# main.net
KiCad netlist of a schematic drawn in EAGLE
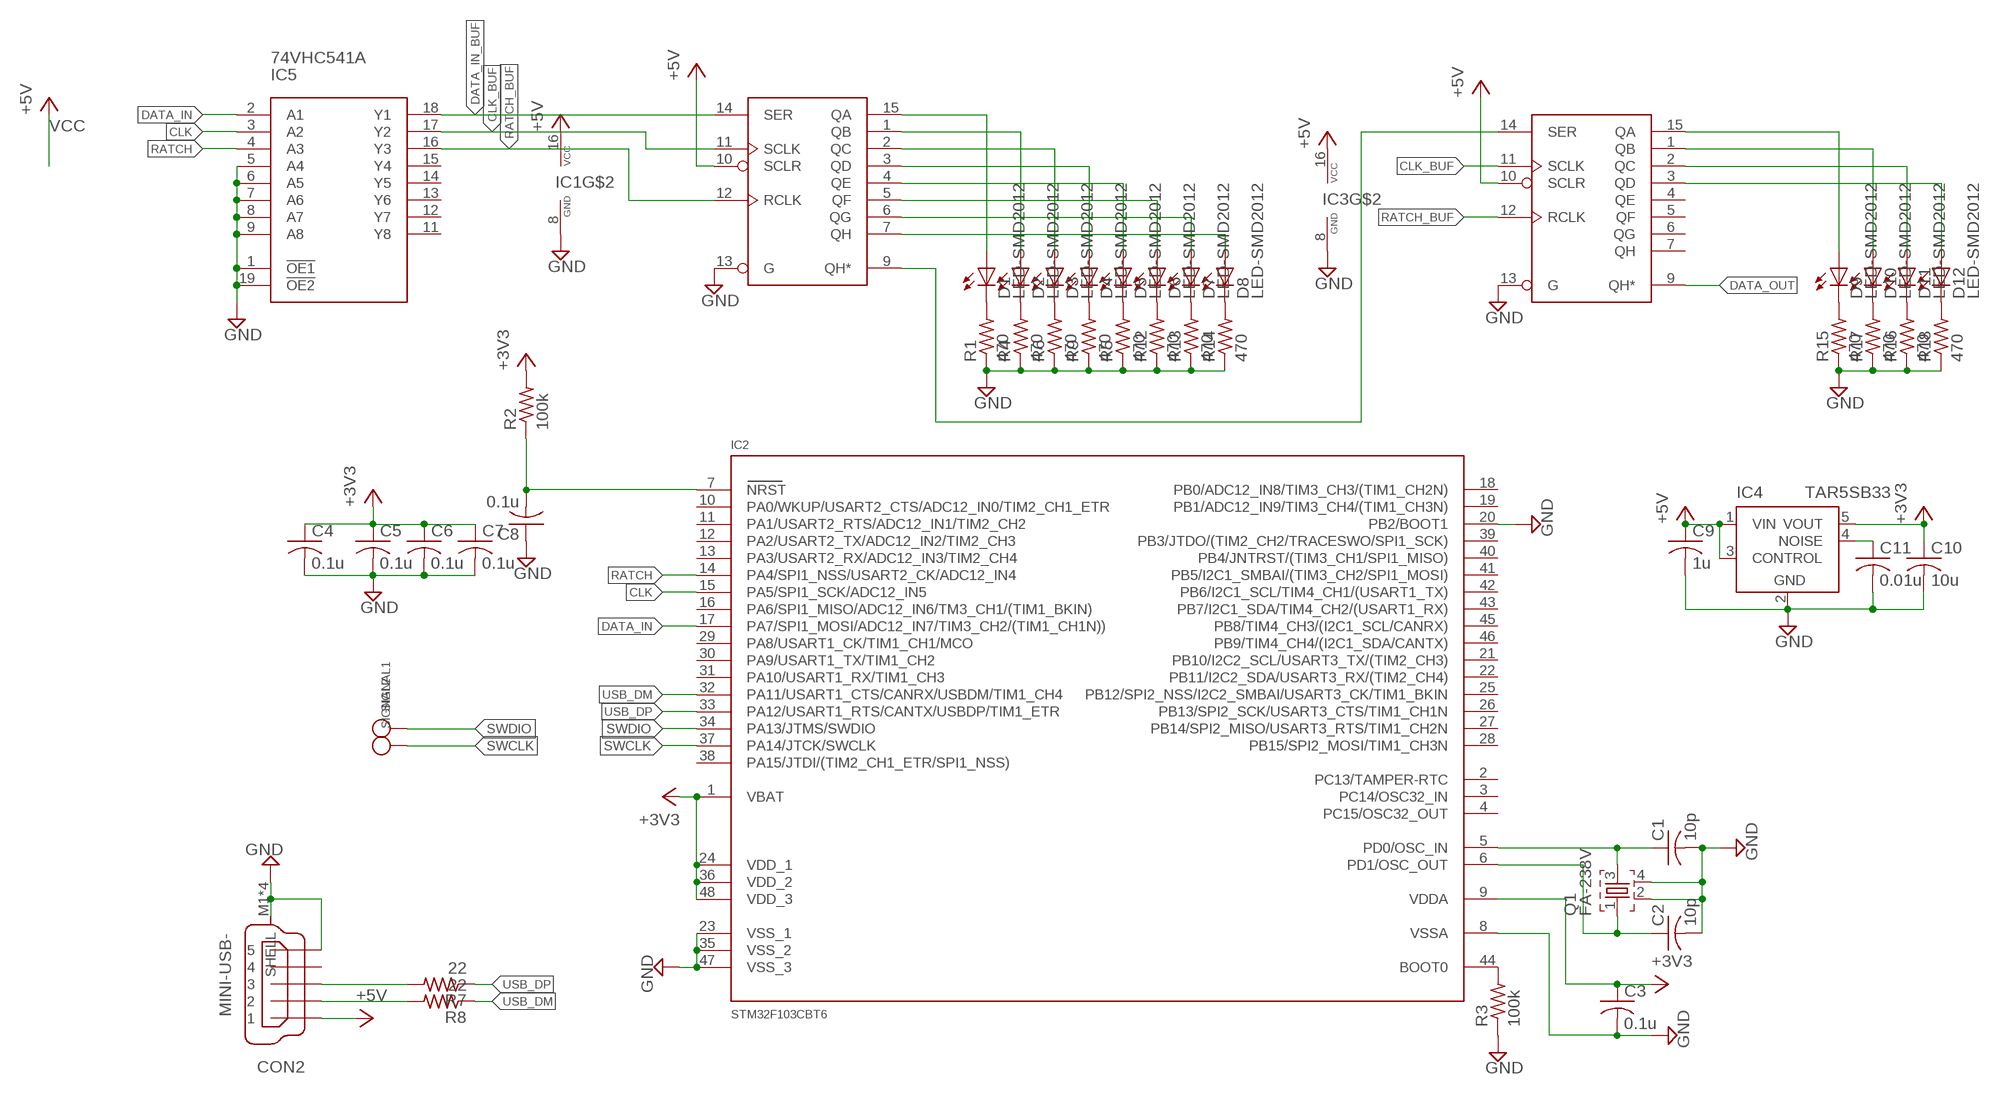
[diagram p0: schematic, sheet 1]

(export (version "E")
  (design (tool "Eeschema 10.0.6"))
  (components
    (comp (ref "C1")
      (value "10p")
      (footprint "eagle-import:1608")
      (libsource (lib "eagle-import") (part "C-1608"))
    )
    (comp (ref "C2")
      (value "10p")
      (footprint "eagle-import:1608")
      (libsource (lib "eagle-import") (part "C-1608"))
    )
    (comp (ref "C3")
      (value "0.1u")
      (footprint "eagle-import:2012-C")
      (libsource (lib "eagle-import") (part "C-2012"))
    )
    (comp (ref "C4")
      (value "0.1u")
      (footprint "eagle-import:2012-C")
      (libsource (lib "eagle-import") (part "C-2012"))
    )
    (comp (ref "C5")
      (value "0.1u")
      (footprint "eagle-import:2012-C")
      (libsource (lib "eagle-import") (part "C-2012"))
    )
    (comp (ref "C6")
      (value "0.1u")
      (footprint "eagle-import:2012-C")
      (libsource (lib "eagle-import") (part "C-2012"))
    )
    (comp (ref "C7")
      (value "0.1u")
      (footprint "eagle-import:2012-C")
      (libsource (lib "eagle-import") (part "C-2012"))
    )
    (comp (ref "C8")
      (value "0.1u")
      (footprint "eagle-import:2012-C")
      (libsource (lib "eagle-import") (part "C-2012"))
    )
    (comp (ref "C9")
      (value "1u")
      (footprint "eagle-import:2012-C")
      (libsource (lib "eagle-import") (part "C-2012"))
    )
    (comp (ref "C10")
      (value "10u")
      (footprint "eagle-import:2012-C")
      (libsource (lib "eagle-import") (part "C-2012"))
    )
    (comp (ref "C11")
      (value "0.01u")
      (footprint "eagle-import:2012-C")
      (libsource (lib "eagle-import") (part "C-2012"))
    )
    (comp (ref "CON2")
      (value "MINI-USB-")
      (footprint "eagle-import:UX60A-MB-5ST")
      (libsource (lib "eagle-import") (part "MINI-USB-"))
    )
    (comp (ref "D1")
      (value "LED-SMD2012")
      (footprint "eagle-import:D2012")
      (libsource (lib "eagle-import") (part "LED-SMD2012"))
    )
    (comp (ref "D2")
      (value "LED-SMD2012")
      (footprint "eagle-import:D2012")
      (libsource (lib "eagle-import") (part "LED-SMD2012"))
    )
    (comp (ref "D3")
      (value "LED-SMD2012")
      (footprint "eagle-import:D2012")
      (libsource (lib "eagle-import") (part "LED-SMD2012"))
    )
    (comp (ref "D4")
      (value "LED-SMD2012")
      (footprint "eagle-import:D2012")
      (libsource (lib "eagle-import") (part "LED-SMD2012"))
    )
    (comp (ref "D5")
      (value "LED-SMD2012")
      (footprint "eagle-import:D2012")
      (libsource (lib "eagle-import") (part "LED-SMD2012"))
    )
    (comp (ref "D6")
      (value "LED-SMD2012")
      (footprint "eagle-import:D2012")
      (libsource (lib "eagle-import") (part "LED-SMD2012"))
    )
    (comp (ref "D7")
      (value "LED-SMD2012")
      (footprint "eagle-import:D2012")
      (libsource (lib "eagle-import") (part "LED-SMD2012"))
    )
    (comp (ref "D8")
      (value "LED-SMD2012")
      (footprint "eagle-import:D2012")
      (libsource (lib "eagle-import") (part "LED-SMD2012"))
    )
    (comp (ref "D9")
      (value "LED-SMD2012")
      (footprint "eagle-import:D2012")
      (libsource (lib "eagle-import") (part "LED-SMD2012"))
    )
    (comp (ref "D10")
      (value "LED-SMD2012")
      (footprint "eagle-import:D2012")
      (libsource (lib "eagle-import") (part "LED-SMD2012"))
    )
    (comp (ref "D11")
      (value "LED-SMD2012")
      (footprint "eagle-import:D2012")
      (libsource (lib "eagle-import") (part "LED-SMD2012"))
    )
    (comp (ref "D12")
      (value "LED-SMD2012")
      (footprint "eagle-import:D2012")
      (libsource (lib "eagle-import") (part "LED-SMD2012"))
    )
    (comp (ref "IC1")
      (value "74595AP")
      (footprint "eagle-import:SOP16")
      (libsource (lib "eagle-import") (part "74595AP"))
    )
    (comp (ref "IC2")
      (value "STM32F103CBT6")
      (footprint "eagle-import:LQFP48")
      (libsource (lib "eagle-import") (part "STM32F103CBT6"))
    )
    (comp (ref "IC3")
      (value "74595AP")
      (footprint "eagle-import:SOP16")
      (libsource (lib "eagle-import") (part "74595AP"))
    )
    (comp (ref "IC4")
      (value "TAR5SB33")
      (footprint "eagle-import:SSOP5-P-0.95")
      (libsource (lib "eagle-import") (part "TAR5SB33"))
    )
    (comp (ref "IC5")
      (value "74VHC541A")
      (footprint "eagle-import:TSSOP20")
      (libsource (lib "eagle-import") (part "74541AVHC"))
    )
    (comp (ref "Q1")
      (value "FA-238V")
      (footprint "eagle-import:FA-238V")
      (libsource (lib "eagle-import") (part "FA-238V"))
    )
    (comp (ref "R1")
      (value "470")
      (footprint "eagle-import:2012-R")
      (libsource (lib "eagle-import") (part "R-2012"))
    )
    (comp (ref "R2")
      (value "100k")
      (footprint "eagle-import:2012-R")
      (libsource (lib "eagle-import") (part "R-2012"))
    )
    (comp (ref "R3")
      (value "100k")
      (footprint "eagle-import:2012-R")
      (libsource (lib "eagle-import") (part "R-2012"))
    )
    (comp (ref "R4")
      (value "470")
      (footprint "eagle-import:2012-R")
      (libsource (lib "eagle-import") (part "R-2012"))
    )
    (comp (ref "R5")
      (value "470")
      (footprint "eagle-import:2012-R")
      (libsource (lib "eagle-import") (part "R-2012"))
    )
    (comp (ref "R6")
      (value "470")
      (footprint "eagle-import:2012-R")
      (libsource (lib "eagle-import") (part "R-2012"))
    )
    (comp (ref "R7")
      (value "22")
      (footprint "eagle-import:2012-R")
      (libsource (lib "eagle-import") (part "R-2012"))
    )
    (comp (ref "R8")
      (value "22")
      (footprint "eagle-import:2012-R")
      (libsource (lib "eagle-import") (part "R-2012"))
    )
    (comp (ref "R9")
      (value "470")
      (footprint "eagle-import:2012-R")
      (libsource (lib "eagle-import") (part "R-2012"))
    )
    (comp (ref "R12")
      (value "470")
      (footprint "eagle-import:2012-R")
      (libsource (lib "eagle-import") (part "R-2012"))
    )
    (comp (ref "R13")
      (value "470")
      (footprint "eagle-import:2012-R")
      (libsource (lib "eagle-import") (part "R-2012"))
    )
    (comp (ref "R14")
      (value "470")
      (footprint "eagle-import:2012-R")
      (libsource (lib "eagle-import") (part "R-2012"))
    )
    (comp (ref "R15")
      (value "470")
      (footprint "eagle-import:2012-R")
      (libsource (lib "eagle-import") (part "R-2012"))
    )
    (comp (ref "R16")
      (value "470")
      (footprint "eagle-import:2012-R")
      (libsource (lib "eagle-import") (part "R-2012"))
    )
    (comp (ref "R17")
      (value "470")
      (footprint "eagle-import:2012-R")
      (libsource (lib "eagle-import") (part "R-2012"))
    )
    (comp (ref "R18")
      (value "470")
      (footprint "eagle-import:2012-R")
      (libsource (lib "eagle-import") (part "R-2012"))
    )
    (comp (ref "SIGNAL1")
      (value "CHECK_PIN-SMD_100*60")
      (footprint "eagle-import:SMD_100_60")
      (libsource (lib "eagle-import") (part "CHECK_PIN-SMD_10060"))
    )
    (comp (ref "SIGNAL2")
      (value "CHECK_PIN-SMD_100*60")
      (footprint "eagle-import:SMD_100_60")
      (libsource (lib "eagle-import") (part "CHECK_PIN-SMD_10060"))
    )
  )
  (nets
    (net (code "1") (name "+3V3") (class "Default")
      (node (ref "C10") (pin "1") (pinfunction "1_1") (pintype "passive"))
      (node (ref "C3") (pin "1") (pinfunction "1_1") (pintype "passive"))
      (node (ref "C4") (pin "1") (pinfunction "1_1") (pintype "passive"))
      (node (ref "C5") (pin "1") (pinfunction "1_1") (pintype "passive"))
      (node (ref "C6") (pin "1") (pinfunction "1_1") (pintype "passive"))
      (node (ref "C7") (pin "1") (pinfunction "1_1") (pintype "passive"))
      (node (ref "IC2") (pin "1") (pinfunction "VBAT_1") (pintype "power_in"))
      (node (ref "IC2") (pin "24") (pinfunction "VDD_1_24") (pintype "power_in"))
      (node (ref "IC2") (pin "36") (pinfunction "VDD_2_36") (pintype "power_in"))
      (node (ref "IC2") (pin "48") (pinfunction "VDD_3_48") (pintype "power_in"))
      (node (ref "IC2") (pin "9") (pinfunction "VDDA_9") (pintype "power_in"))
      (node (ref "IC4") (pin "5") (pinfunction "VOUT_5") (pintype "power_in"))
      (node (ref "R2") (pin "2") (pinfunction "2_2") (pintype "passive"))
    )
    (net (code "2") (name "+5V") (class "Default")
      (node (ref "C9") (pin "1") (pinfunction "1_1") (pintype "passive"))
      (node (ref "CON2") (pin "1") (pinfunction "1_1") (pintype "input"))
      (node (ref "IC1") (pin "10") (pinfunction "SCLR_10") (pintype "input"))
      (node (ref "IC1") (pin "16") (pinfunction "VCC_16") (pintype "power_in"))
      (node (ref "IC3") (pin "10") (pinfunction "SCLR_10") (pintype "input"))
      (node (ref "IC3") (pin "16") (pinfunction "VCC_16") (pintype "power_in"))
      (node (ref "IC4") (pin "1") (pinfunction "VIN_1") (pintype "input"))
      (node (ref "IC4") (pin "3") (pinfunction "CONTROL_3") (pintype "input"))
    )
    (net (code "3") (name "CLK") (class "Default")
      (node (ref "IC2") (pin "15") (pinfunction "PA5/SPI1_SCK/ADC12_IN5_15") (pintype "bidirectional"))
      (node (ref "IC5") (pin "3") (pinfunction "A2_3") (pintype "bidirectional"))
    )
    (net (code "4") (name "CLK_BUF") (class "Default")
      (node (ref "IC1") (pin "11") (pinfunction "SCLK_11") (pintype "input"))
      (node (ref "IC3") (pin "11") (pinfunction "SCLK_11") (pintype "input"))
      (node (ref "IC5") (pin "17") (pinfunction "Y2_17") (pintype "bidirectional"))
    )
    (net (code "5") (name "DATA_IN") (class "Default")
      (node (ref "IC2") (pin "17") (pinfunction "PA7/SPI1_MOSI/ADC12_IN7/TIM3_CH2/(TIM1_CH1N))_17") (pintype "bidirectional"))
      (node (ref "IC5") (pin "2") (pinfunction "A1_2") (pintype "bidirectional"))
    )
    (net (code "6") (name "DATA_IN_BUF") (class "Default")
      (node (ref "IC1") (pin "14") (pinfunction "SER_14") (pintype "input"))
      (node (ref "IC5") (pin "18") (pinfunction "Y1_18") (pintype "bidirectional"))
    )
    (net (code "7") (name "DATA_OUT") (class "Default")
      (node (ref "IC3") (pin "9") (pinfunction "QH*_9") (pintype "output"))
    )
    (net (code "8") (name "GND") (class "Default")
      (node (ref "C1") (pin "2") (pinfunction "2_2") (pintype "passive"))
      (node (ref "C10") (pin "2") (pinfunction "2_2") (pintype "passive"))
      (node (ref "C11") (pin "2") (pinfunction "2_2") (pintype "passive"))
      (node (ref "C2") (pin "2") (pinfunction "2_2") (pintype "passive"))
      (node (ref "C3") (pin "2") (pinfunction "2_2") (pintype "passive"))
      (node (ref "C4") (pin "2") (pinfunction "2_2") (pintype "passive"))
      (node (ref "C5") (pin "2") (pinfunction "2_2") (pintype "passive"))
      (node (ref "C6") (pin "2") (pinfunction "2_2") (pintype "passive"))
      (node (ref "C7") (pin "2") (pinfunction "2_2") (pintype "passive"))
      (node (ref "C8") (pin "1") (pinfunction "1_1") (pintype "passive"))
      (node (ref "C9") (pin "2") (pinfunction "2_2") (pintype "passive"))
      (node (ref "CON2") (pin "5") (pinfunction "5_5") (pintype "input"))
      (node (ref "CON2") (pin "M1") (pinfunction "SHELL_M1") (pintype "bidirectional"))
      (node (ref "CON2") (pin "M2") (pinfunction "SHELL_M2") (pintype "bidirectional"))
      (node (ref "CON2") (pin "M3") (pinfunction "SHELL_M3") (pintype "bidirectional"))
      (node (ref "CON2") (pin "M4") (pinfunction "SHELL_M4") (pintype "bidirectional"))
      (node (ref "IC1") (pin "13") (pinfunction "G_13") (pintype "input"))
      (node (ref "IC1") (pin "8") (pinfunction "GND_8") (pintype "power_in"))
      (node (ref "IC2") (pin "20") (pinfunction "PB2/BOOT1_20") (pintype "bidirectional"))
      (node (ref "IC2") (pin "23") (pinfunction "VSS_1_23") (pintype "power_in"))
      (node (ref "IC2") (pin "35") (pinfunction "VSS_2_35") (pintype "power_in"))
      (node (ref "IC2") (pin "47") (pinfunction "VSS_3_47") (pintype "power_in"))
      (node (ref "IC2") (pin "8") (pinfunction "VSSA_8") (pintype "power_in"))
      (node (ref "IC3") (pin "13") (pinfunction "G_13") (pintype "input"))
      (node (ref "IC3") (pin "8") (pinfunction "GND_8") (pintype "power_in"))
      (node (ref "IC4") (pin "2") (pinfunction "GND_2") (pintype "power_in"))
      (node (ref "IC5") (pin "1") (pinfunction "~{OE1}_1") (pintype "bidirectional"))
      (node (ref "IC5") (pin "19") (pinfunction "~{OE2}_19") (pintype "bidirectional"))
      (node (ref "IC5") (pin "5") (pinfunction "A4_5") (pintype "bidirectional"))
      (node (ref "IC5") (pin "6") (pinfunction "A5_6") (pintype "bidirectional"))
      (node (ref "IC5") (pin "7") (pinfunction "A6_7") (pintype "bidirectional"))
      (node (ref "IC5") (pin "8") (pinfunction "A7_8") (pintype "bidirectional"))
      (node (ref "IC5") (pin "9") (pinfunction "A8_9") (pintype "bidirectional"))
      (node (ref "Q1") (pin "2") (pinfunction "2_2") (pintype "passive"))
      (node (ref "Q1") (pin "4") (pinfunction "4_4") (pintype "passive"))
      (node (ref "R1") (pin "1") (pinfunction "1_1") (pintype "passive"))
      (node (ref "R12") (pin "1") (pinfunction "1_1") (pintype "passive"))
      (node (ref "R13") (pin "1") (pinfunction "1_1") (pintype "passive"))
      (node (ref "R14") (pin "1") (pinfunction "1_1") (pintype "passive"))
      (node (ref "R15") (pin "1") (pinfunction "1_1") (pintype "passive"))
      (node (ref "R16") (pin "1") (pinfunction "1_1") (pintype "passive"))
      (node (ref "R17") (pin "1") (pinfunction "1_1") (pintype "passive"))
      (node (ref "R18") (pin "1") (pinfunction "1_1") (pintype "passive"))
      (node (ref "R3") (pin "1") (pinfunction "1_1") (pintype "passive"))
      (node (ref "R4") (pin "1") (pinfunction "1_1") (pintype "passive"))
      (node (ref "R5") (pin "1") (pinfunction "1_1") (pintype "passive"))
      (node (ref "R6") (pin "1") (pinfunction "1_1") (pintype "passive"))
      (node (ref "R9") (pin "1") (pinfunction "1_1") (pintype "passive"))
    )
    (net (code "9") (name "Net-(CON2-Pad2)") (class "Default")
      (node (ref "CON2") (pin "2") (pinfunction "2_2") (pintype "input"))
      (node (ref "R8") (pin "2") (pinfunction "2_2") (pintype "passive"))
    )
    (net (code "10") (name "Net-(CON2-Pad3)") (class "Default")
      (node (ref "CON2") (pin "3") (pinfunction "3_3") (pintype "input"))
      (node (ref "R7") (pin "2") (pinfunction "2_2") (pintype "passive"))
    )
    (net (code "11") (name "Net-(D1-PadK)") (class "Default")
      (node (ref "D1") (pin "K") (pinfunction "K_K") (pintype "passive"))
      (node (ref "R1") (pin "2") (pinfunction "2_2") (pintype "passive"))
    )
    (net (code "12") (name "Net-(D2-PadK)") (class "Default")
      (node (ref "D2") (pin "K") (pinfunction "K_K") (pintype "passive"))
      (node (ref "R4") (pin "2") (pinfunction "2_2") (pintype "passive"))
    )
    (net (code "13") (name "Net-(D3-PadK)") (class "Default")
      (node (ref "D3") (pin "K") (pinfunction "K_K") (pintype "passive"))
      (node (ref "R6") (pin "2") (pinfunction "2_2") (pintype "passive"))
    )
    (net (code "14") (name "Net-(D4-PadK)") (class "Default")
      (node (ref "D4") (pin "K") (pinfunction "K_K") (pintype "passive"))
      (node (ref "R9") (pin "2") (pinfunction "2_2") (pintype "passive"))
    )
    (net (code "15") (name "Net-(D5-PadK)") (class "Default")
      (node (ref "D5") (pin "K") (pinfunction "K_K") (pintype "passive"))
      (node (ref "R5") (pin "2") (pinfunction "2_2") (pintype "passive"))
    )
    (net (code "16") (name "Net-(D6-PadK)") (class "Default")
      (node (ref "D6") (pin "K") (pinfunction "K_K") (pintype "passive"))
      (node (ref "R12") (pin "2") (pinfunction "2_2") (pintype "passive"))
    )
    (net (code "17") (name "Net-(D7-PadK)") (class "Default")
      (node (ref "D7") (pin "K") (pinfunction "K_K") (pintype "passive"))
      (node (ref "R13") (pin "2") (pinfunction "2_2") (pintype "passive"))
    )
    (net (code "18") (name "Net-(D8-PadK)") (class "Default")
      (node (ref "D8") (pin "K") (pinfunction "K_K") (pintype "passive"))
      (node (ref "R14") (pin "2") (pinfunction "2_2") (pintype "passive"))
    )
    (net (code "19") (name "Net-(D9-PadK)") (class "Default")
      (node (ref "D9") (pin "K") (pinfunction "K_K") (pintype "passive"))
      (node (ref "R15") (pin "2") (pinfunction "2_2") (pintype "passive"))
    )
    (net (code "20") (name "Net-(D10-PadK)") (class "Default")
      (node (ref "D10") (pin "K") (pinfunction "K_K") (pintype "passive"))
      (node (ref "R17") (pin "2") (pinfunction "2_2") (pintype "passive"))
    )
    (net (code "21") (name "Net-(D11-PadK)") (class "Default")
      (node (ref "D11") (pin "K") (pinfunction "K_K") (pintype "passive"))
      (node (ref "R16") (pin "2") (pinfunction "2_2") (pintype "passive"))
    )
    (net (code "22") (name "Net-(D12-PadK)") (class "Default")
      (node (ref "D12") (pin "K") (pinfunction "K_K") (pintype "passive"))
      (node (ref "R18") (pin "2") (pinfunction "2_2") (pintype "passive"))
    )
    (net (code "23") (name "Net-(IC1A-QA)") (class "Default")
      (node (ref "D1") (pin "A") (pinfunction "A_A") (pintype "passive"))
      (node (ref "IC1") (pin "15") (pinfunction "QA_15") (pintype "output"))
    )
    (net (code "24") (name "Net-(IC1A-QB)") (class "Default")
      (node (ref "D2") (pin "A") (pinfunction "A_A") (pintype "passive"))
      (node (ref "IC1") (pin "1") (pinfunction "QB_1") (pintype "output"))
    )
    (net (code "25") (name "Net-(IC1A-QC)") (class "Default")
      (node (ref "D3") (pin "A") (pinfunction "A_A") (pintype "passive"))
      (node (ref "IC1") (pin "2") (pinfunction "QC_2") (pintype "output"))
    )
    (net (code "26") (name "Net-(IC1A-QD)") (class "Default")
      (node (ref "D4") (pin "A") (pinfunction "A_A") (pintype "passive"))
      (node (ref "IC1") (pin "3") (pinfunction "QD_3") (pintype "output"))
    )
    (net (code "27") (name "Net-(IC1A-QE)") (class "Default")
      (node (ref "D5") (pin "A") (pinfunction "A_A") (pintype "passive"))
      (node (ref "IC1") (pin "4") (pinfunction "QE_4") (pintype "output"))
    )
    (net (code "28") (name "Net-(IC1A-QF)") (class "Default")
      (node (ref "D6") (pin "A") (pinfunction "A_A") (pintype "passive"))
      (node (ref "IC1") (pin "5") (pinfunction "QF_5") (pintype "output"))
    )
    (net (code "29") (name "Net-(IC1A-QG)") (class "Default")
      (node (ref "D7") (pin "A") (pinfunction "A_A") (pintype "passive"))
      (node (ref "IC1") (pin "6") (pinfunction "QG_6") (pintype "output"))
    )
    (net (code "30") (name "Net-(IC1A-QH)") (class "Default")
      (node (ref "D8") (pin "A") (pinfunction "A_A") (pintype "passive"))
      (node (ref "IC1") (pin "7") (pinfunction "QH_7") (pintype "output"))
    )
    (net (code "31") (name "Net-(IC1A-QH*)") (class "Default")
      (node (ref "IC1") (pin "9") (pinfunction "QH*_9") (pintype "output"))
      (node (ref "IC3") (pin "14") (pinfunction "SER_14") (pintype "input"))
    )
    (net (code "32") (name "Net-(IC2-BOOT0)") (class "Default")
      (node (ref "IC2") (pin "44") (pinfunction "BOOT0_44") (pintype "input"))
      (node (ref "R3") (pin "2") (pinfunction "2_2") (pintype "passive"))
    )
    (net (code "33") (name "Net-(IC2-NRST)") (class "Default")
      (node (ref "C8") (pin "2") (pinfunction "2_2") (pintype "passive"))
      (node (ref "IC2") (pin "7") (pinfunction "NRST_7") (pintype "bidirectional"))
      (node (ref "R2") (pin "1") (pinfunction "1_1") (pintype "passive"))
    )
    (net (code "34") (name "Net-(IC2-PD0{slash}OSC_IN)") (class "Default")
      (node (ref "C1") (pin "1") (pinfunction "1_1") (pintype "passive"))
      (node (ref "IC2") (pin "5") (pinfunction "PD0/OSC_IN_5") (pintype "bidirectional"))
      (node (ref "Q1") (pin "3") (pinfunction "3_3") (pintype "passive"))
    )
    (net (code "35") (name "Net-(IC2-PD1{slash}OSC_OUT)") (class "Default")
      (node (ref "C2") (pin "1") (pinfunction "1_1") (pintype "passive"))
      (node (ref "IC2") (pin "6") (pinfunction "PD1/OSC_OUT_6") (pintype "bidirectional"))
      (node (ref "Q1") (pin "1") (pinfunction "1_1") (pintype "passive"))
    )
    (net (code "36") (name "Net-(IC3A-QA)") (class "Default")
      (node (ref "D9") (pin "A") (pinfunction "A_A") (pintype "passive"))
      (node (ref "IC3") (pin "15") (pinfunction "QA_15") (pintype "output"))
    )
    (net (code "37") (name "Net-(IC3A-QB)") (class "Default")
      (node (ref "D10") (pin "A") (pinfunction "A_A") (pintype "passive"))
      (node (ref "IC3") (pin "1") (pinfunction "QB_1") (pintype "output"))
    )
    (net (code "38") (name "Net-(IC3A-QC)") (class "Default")
      (node (ref "D11") (pin "A") (pinfunction "A_A") (pintype "passive"))
      (node (ref "IC3") (pin "2") (pinfunction "QC_2") (pintype "output"))
    )
    (net (code "39") (name "Net-(IC3A-QD)") (class "Default")
      (node (ref "D12") (pin "A") (pinfunction "A_A") (pintype "passive"))
      (node (ref "IC3") (pin "3") (pinfunction "QD_3") (pintype "output"))
    )
    (net (code "40") (name "Net-(IC4-NOISE)") (class "Default")
      (node (ref "C11") (pin "1") (pinfunction "1_1") (pintype "passive"))
      (node (ref "IC4") (pin "4") (pinfunction "NOISE_4") (pintype "passive"))
    )
    (net (code "41") (name "RATCH") (class "Default")
      (node (ref "IC2") (pin "14") (pinfunction "PA4/SPI1_NSS/USART2_CK/ADC12_IN4_14") (pintype "bidirectional"))
      (node (ref "IC5") (pin "4") (pinfunction "A3_4") (pintype "bidirectional"))
    )
    (net (code "42") (name "RATCH_BUF") (class "Default")
      (node (ref "IC1") (pin "12") (pinfunction "RCLK_12") (pintype "input"))
      (node (ref "IC3") (pin "12") (pinfunction "RCLK_12") (pintype "input"))
      (node (ref "IC5") (pin "16") (pinfunction "Y3_16") (pintype "bidirectional"))
    )
    (net (code "43") (name "SWCLK") (class "Default")
      (node (ref "IC2") (pin "37") (pinfunction "PA14/JTCK/SWCLK_37") (pintype "bidirectional"))
      (node (ref "SIGNAL2") (pin "SIGNAL") (pinfunction "SIGNAL_SIGNAL") (pintype "bidirectional"))
    )
    (net (code "44") (name "SWDIO") (class "Default")
      (node (ref "IC2") (pin "34") (pinfunction "PA13/JTMS/SWDIO_34") (pintype "bidirectional"))
      (node (ref "SIGNAL1") (pin "SIGNAL") (pinfunction "SIGNAL_SIGNAL") (pintype "bidirectional"))
    )
    (net (code "45") (name "USB_DM") (class "Default")
      (node (ref "IC2") (pin "32") (pinfunction "PA11/USART1_CTS/CANRX/USBDM/TIM1_CH4_32") (pintype "bidirectional"))
      (node (ref "R8") (pin "1") (pinfunction "1_1") (pintype "passive"))
    )
    (net (code "46") (name "USB_DP") (class "Default")
      (node (ref "IC2") (pin "33") (pinfunction "PA12/USART1_RTS/CANTX/USBDP/TIM1_ETR_33") (pintype "bidirectional"))
      (node (ref "R7") (pin "1") (pinfunction "1_1") (pintype "passive"))
    )
    (net (code "47") (name "unconnected-(CON2-Pad4)") (class "Default")
      (node (ref "CON2") (pin "4") (pinfunction "4_4") (pintype "input"))
    )
    (net (code "48") (name "unconnected-(IC2-PA0{slash}WKUP{slash}USART2_CTS{slash}ADC12_IN0{slash}TIM2_CH1_ETR-Pad10)") (class "Default")
      (node (ref "IC2") (pin "10") (pinfunction "PA0/WKUP/USART2_CTS/ADC12_IN0/TIM2_CH1_ETR_10") (pintype "bidirectional"))
    )
    (net (code "49") (name "unconnected-(IC2-PA1{slash}USART2_RTS{slash}ADC12_IN1{slash}TIM2_CH2-Pad11)") (class "Default")
      (node (ref "IC2") (pin "11") (pinfunction "PA1/USART2_RTS/ADC12_IN1/TIM2_CH2_11") (pintype "bidirectional"))
    )
    (net (code "50") (name "unconnected-(IC2-PA2{slash}USART2_TX{slash}ADC12_IN2{slash}TIM2_CH3-Pad12)") (class "Default")
      (node (ref "IC2") (pin "12") (pinfunction "PA2/USART2_TX/ADC12_IN2/TIM2_CH3_12") (pintype "bidirectional"))
    )
    (net (code "51") (name "unconnected-(IC2-PA3{slash}USART2_RX{slash}ADC12_IN3{slash}TIM2_CH4-Pad13)") (class "Default")
      (node (ref "IC2") (pin "13") (pinfunction "PA3/USART2_RX/ADC12_IN3/TIM2_CH4_13") (pintype "bidirectional"))
    )
    (net (code "52") (name "unconnected-(IC2-PA6{slash}SPI1_MISO{slash}ADC12_IN6{slash}TM3_CH1{slash}(TIM1_BKIN)-Pad16)") (class "Default")
      (node (ref "IC2") (pin "16") (pinfunction "PA6/SPI1_MISO/ADC12_IN6/TM3_CH1/(TIM1_BKIN)_16") (pintype "bidirectional"))
    )
    (net (code "53") (name "unconnected-(IC2-PA8{slash}USART1_CK{slash}TIM1_CH1{slash}MCO-Pad29)") (class "Default")
      (node (ref "IC2") (pin "29") (pinfunction "PA8/USART1_CK/TIM1_CH1/MCO_29") (pintype "bidirectional"))
    )
    (net (code "54") (name "unconnected-(IC2-PA9{slash}USART1_TX{slash}TIM1_CH2-Pad30)") (class "Default")
      (node (ref "IC2") (pin "30") (pinfunction "PA9/USART1_TX/TIM1_CH2_30") (pintype "bidirectional"))
    )
    (net (code "55") (name "unconnected-(IC2-PA10{slash}USART1_RX{slash}TIM1_CH3-Pad31)") (class "Default")
      (node (ref "IC2") (pin "31") (pinfunction "PA10/USART1_RX/TIM1_CH3_31") (pintype "bidirectional"))
    )
    (net (code "56") (name "unconnected-(IC2-PA15{slash}JTDI{slash}(TIM2_CH1_ETR{slash}SPI1_NSS)-Pad38)") (class "Default")
      (node (ref "IC2") (pin "38") (pinfunction "PA15/JTDI/(TIM2_CH1_ETR/SPI1_NSS)_38") (pintype "bidirectional"))
    )
    (net (code "57") (name "unconnected-(IC2-PB0{slash}ADC12_IN8{slash}TIM3_CH3{slash}(TIM1_CH2N)-Pad18)") (class "Default")
      (node (ref "IC2") (pin "18") (pinfunction "PB0/ADC12_IN8/TIM3_CH3/(TIM1_CH2N)_18") (pintype "bidirectional"))
    )
    (net (code "58") (name "unconnected-(IC2-PB1{slash}ADC12_IN9{slash}TIM3_CH4{slash}(TIM1_CH3N)-Pad19)") (class "Default")
      (node (ref "IC2") (pin "19") (pinfunction "PB1/ADC12_IN9/TIM3_CH4/(TIM1_CH3N)_19") (pintype "bidirectional"))
    )
    (net (code "59") (name "unconnected-(IC2-PB3{slash}JTDO{slash}(TIM2_CH2{slash}TRACESWO{slash}SPI1_SCK)-Pad39)") (class "Default")
      (node (ref "IC2") (pin "39") (pinfunction "PB3/JTDO/(TIM2_CH2/TRACESWO/SPI1_SCK)_39") (pintype "bidirectional"))
    )
    (net (code "60") (name "unconnected-(IC2-PB4{slash}JNTRST{slash}(TIM3_CH1{slash}SPI1_MISO)-Pad40)") (class "Default")
      (node (ref "IC2") (pin "40") (pinfunction "PB4/JNTRST/(TIM3_CH1/SPI1_MISO)_40") (pintype "bidirectional"))
    )
    (net (code "61") (name "unconnected-(IC2-PB5{slash}I2C1_SMBAI{slash}(TIM3_CH2{slash}SPI1_MOSI)-Pad41)") (class "Default")
      (node (ref "IC2") (pin "41") (pinfunction "PB5/I2C1_SMBAI/(TIM3_CH2/SPI1_MOSI)_41") (pintype "bidirectional"))
    )
    (net (code "62") (name "unconnected-(IC2-PB6{slash}I2C1_SCL{slash}TIM4_CH1{slash}(USART1_TX)-Pad42)") (class "Default")
      (node (ref "IC2") (pin "42") (pinfunction "PB6/I2C1_SCL/TIM4_CH1/(USART1_TX)_42") (pintype "bidirectional"))
    )
    (net (code "63") (name "unconnected-(IC2-PB7{slash}I2C1_SDA{slash}TIM4_CH2{slash}(USART1_RX)-Pad43)") (class "Default")
      (node (ref "IC2") (pin "43") (pinfunction "PB7/I2C1_SDA/TIM4_CH2/(USART1_RX)_43") (pintype "bidirectional"))
    )
    (net (code "64") (name "unconnected-(IC2-PB8{slash}TIM4_CH3{slash}(I2C1_SCL{slash}CANRX)-Pad45)") (class "Default")
      (node (ref "IC2") (pin "45") (pinfunction "PB8/TIM4_CH3/(I2C1_SCL/CANRX)_45") (pintype "bidirectional"))
    )
    (net (code "65") (name "unconnected-(IC2-PB9{slash}TIM4_CH4{slash}(I2C1_SDA{slash}CANTX)-Pad46)") (class "Default")
      (node (ref "IC2") (pin "46") (pinfunction "PB9/TIM4_CH4/(I2C1_SDA/CANTX)_46") (pintype "bidirectional"))
    )
    (net (code "66") (name "unconnected-(IC2-PB10{slash}I2C2_SCL{slash}USART3_TX{slash}(TIM2_CH3)-Pad21)") (class "Default")
      (node (ref "IC2") (pin "21") (pinfunction "PB10/I2C2_SCL/USART3_TX/(TIM2_CH3)_21") (pintype "bidirectional"))
    )
    (net (code "67") (name "unconnected-(IC2-PB11{slash}I2C2_SDA{slash}USART3_RX{slash}(TIM2_CH4)-Pad22)") (class "Default")
      (node (ref "IC2") (pin "22") (pinfunction "PB11/I2C2_SDA/USART3_RX/(TIM2_CH4)_22") (pintype "bidirectional"))
    )
    (net (code "68") (name "unconnected-(IC2-PB12{slash}SPI2_NSS{slash}I2C2_SMBAI{slash}USART3_CK{slash}TIM1_BKIN-Pad25)") (class "Default")
      (node (ref "IC2") (pin "25") (pinfunction "PB12/SPI2_NSS/I2C2_SMBAI/USART3_CK/TIM1_BKIN_25") (pintype "bidirectional"))
    )
    (net (code "69") (name "unconnected-(IC2-PB13{slash}SPI2_SCK{slash}USART3_CTS{slash}TIM1_CH1N-Pad26)") (class "Default")
      (node (ref "IC2") (pin "26") (pinfunction "PB13/SPI2_SCK/USART3_CTS/TIM1_CH1N_26") (pintype "bidirectional"))
    )
    (net (code "70") (name "unconnected-(IC2-PB14{slash}SPI2_MISO{slash}USART3_RTS{slash}TIM1_CH2N-Pad27)") (class "Default")
      (node (ref "IC2") (pin "27") (pinfunction "PB14/SPI2_MISO/USART3_RTS/TIM1_CH2N_27") (pintype "bidirectional"))
    )
    (net (code "71") (name "unconnected-(IC2-PB15{slash}SPI2_MOSI{slash}TIM1_CH3N-Pad28)") (class "Default")
      (node (ref "IC2") (pin "28") (pinfunction "PB15/SPI2_MOSI/TIM1_CH3N_28") (pintype "bidirectional"))
    )
    (net (code "72") (name "unconnected-(IC2-PC13{slash}TAMPER-RTC-Pad2)") (class "Default")
      (node (ref "IC2") (pin "2") (pinfunction "PC13/TAMPER-RTC_2") (pintype "bidirectional"))
    )
    (net (code "73") (name "unconnected-(IC2-PC14{slash}OSC32_IN-Pad3)") (class "Default")
      (node (ref "IC2") (pin "3") (pinfunction "PC14/OSC32_IN_3") (pintype "bidirectional"))
    )
    (net (code "74") (name "unconnected-(IC2-PC15{slash}OSC32_OUT-Pad4)") (class "Default")
      (node (ref "IC2") (pin "4") (pinfunction "PC15/OSC32_OUT_4") (pintype "bidirectional"))
    )
    (net (code "75") (name "unconnected-(IC3A-QE-Pad4)") (class "Default")
      (node (ref "IC3") (pin "4") (pinfunction "QE_4") (pintype "output"))
    )
    (net (code "76") (name "unconnected-(IC3A-QF-Pad5)") (class "Default")
      (node (ref "IC3") (pin "5") (pinfunction "QF_5") (pintype "output"))
    )
    (net (code "77") (name "unconnected-(IC3A-QG-Pad6)") (class "Default")
      (node (ref "IC3") (pin "6") (pinfunction "QG_6") (pintype "output"))
    )
    (net (code "78") (name "unconnected-(IC3A-QH-Pad7)") (class "Default")
      (node (ref "IC3") (pin "7") (pinfunction "QH_7") (pintype "output"))
    )
    (net (code "79") (name "unconnected-(IC5A-Y4-Pad15)") (class "Default")
      (node (ref "IC5") (pin "15") (pinfunction "Y4_15") (pintype "bidirectional"))
    )
    (net (code "80") (name "unconnected-(IC5A-Y5-Pad14)") (class "Default")
      (node (ref "IC5") (pin "14") (pinfunction "Y5_14") (pintype "bidirectional"))
    )
    (net (code "81") (name "unconnected-(IC5A-Y6-Pad13)") (class "Default")
      (node (ref "IC5") (pin "13") (pinfunction "Y6_13") (pintype "bidirectional"))
    )
    (net (code "82") (name "unconnected-(IC5A-Y7-Pad12)") (class "Default")
      (node (ref "IC5") (pin "12") (pinfunction "Y7_12") (pintype "bidirectional"))
    )
    (net (code "83") (name "unconnected-(IC5A-Y8-Pad11)") (class "Default")
      (node (ref "IC5") (pin "11") (pinfunction "Y8_11") (pintype "bidirectional"))
    )
  )
)
